# relay_driver.net
KiCad netlist of a schematic drawn in EAGLE
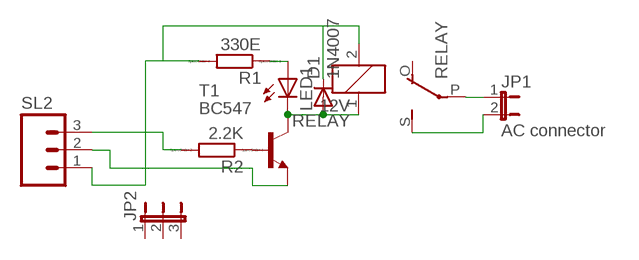
[diagram p0: schematic, sheet 1]

(export (version "E")
  (design (tool "Eeschema 10.0.6"))
  (components
    (comp (ref "D1")
      (value "1N4007")
      (footprint "eagle-import:DO41-10")
      (libsource (lib "eagle-import") (part "1N4004"))
    )
    (comp (ref "JP1")
      (value "AC connector")
      (footprint "eagle-import:JP1")
      (libsource (lib "eagle-import") (part "JP1E"))
    )
    (comp (ref "JP2")
      (value "JP2E")
      (footprint "eagle-import:JP2")
      (libsource (lib "eagle-import") (part "JP2E"))
    )
    (comp (ref "LED1")
      (value "LED3MM")
      (footprint "eagle-import:LED3MM")
      (libsource (lib "eagle-import") (part "LED3MM"))
    )
    (comp (ref "R1")
      (value "330E")
      (footprint "eagle-import:0204_7")
      (libsource (lib "eagle-import") (part "R0204/7"))
    )
    (comp (ref "R2")
      (value "2.2K")
      (footprint "eagle-import:0204_7")
      (libsource (lib "eagle-import") (part "R0204/7"))
    )
    (comp (ref "RELAY")
      (value "12V")
      (footprint "eagle-import:G5LE")
      (libsource (lib "eagle-import") (part "G5L"))
    )
    (comp (ref "SL2")
      (value "M03")
      (footprint "eagle-import:03P")
      (libsource (lib "eagle-import") (part "M03"))
    )
    (comp (ref "T1")
      (value "BC547")
      (footprint "eagle-import:TO92")
      (libsource (lib "eagle-import") (part "BC547"))
    )
  )
  (nets
    (net (code "1") (name "Net-(D1-PadC)") (class "Default")
      (node (ref "D1") (pin "C") (pinfunction "C_C") (pintype "passive"))
      (node (ref "R1") (pin "2") (pinfunction "2_2") (pintype "passive"))
      (node (ref "RELAY") (pin "2") (pinfunction "2_2") (pintype "passive"))
      (node (ref "SL2") (pin "1") (pinfunction "1_1") (pintype "passive"))
    )
    (net (code "2") (name "Net-(JP1-Pad1)") (class "Default")
      (node (ref "JP1") (pin "1") (pinfunction "1_1") (pintype "passive"))
      (node (ref "RELAY") (pin "P") (pinfunction "P_P") (pintype "passive"))
    )
    (net (code "3") (name "Net-(JP1-Pad2)") (class "Default")
      (node (ref "JP1") (pin "2") (pinfunction "2_2") (pintype "passive"))
      (node (ref "RELAY") (pin "S") (pinfunction "S_S") (pintype "passive"))
    )
    (net (code "4") (name "Net-(LED1-C)") (class "Default")
      (node (ref "D1") (pin "A") (pinfunction "A_A") (pintype "passive"))
      (node (ref "LED1") (pin "K") (pinfunction "C_K") (pintype "passive"))
      (node (ref "RELAY") (pin "1") (pinfunction "1_1") (pintype "passive"))
      (node (ref "T1") (pin "3") (pinfunction "C_3") (pintype "passive"))
    )
    (net (code "5") (name "Net-(LED1-PadA)") (class "Default")
      (node (ref "LED1") (pin "A") (pinfunction "A_A") (pintype "passive"))
      (node (ref "R1") (pin "1") (pinfunction "1_1") (pintype "passive"))
    )
    (net (code "6") (name "Net-(R2-Pad2)") (class "Default")
      (node (ref "R2") (pin "2") (pinfunction "2_2") (pintype "passive"))
      (node (ref "SL2") (pin "3") (pinfunction "3_3") (pintype "passive"))
    )
    (net (code "7") (name "Net-(T1-B)") (class "Default")
      (node (ref "R2") (pin "1") (pinfunction "1_1") (pintype "passive"))
      (node (ref "T1") (pin "2") (pinfunction "B_2") (pintype "passive"))
    )
    (net (code "8") (name "Net-(T1-E)") (class "Default")
      (node (ref "SL2") (pin "2") (pinfunction "2_2") (pintype "passive"))
      (node (ref "T1") (pin "1") (pinfunction "E_1") (pintype "passive"))
    )
    (net (code "9") (name "unconnected-(JP2-Pad1)") (class "Default")
      (node (ref "JP2") (pin "1") (pinfunction "1_1") (pintype "passive"))
    )
    (net (code "10") (name "unconnected-(JP2-Pad2)") (class "Default")
      (node (ref "JP2") (pin "2") (pinfunction "2_2") (pintype "passive"))
    )
    (net (code "11") (name "unconnected-(JP2-Pad3)") (class "Default")
      (node (ref "JP2") (pin "3") (pinfunction "3_3") (pintype "passive"))
    )
    (net (code "12") (name "unconnected-(RELAY-PadO)") (class "Default")
      (node (ref "RELAY") (pin "O") (pinfunction "O_O") (pintype "passive"))
    )
  )
)
